# 02_CPU_SYSTEM.net
KiCad netlist of a schematic drawn in Altium Designer
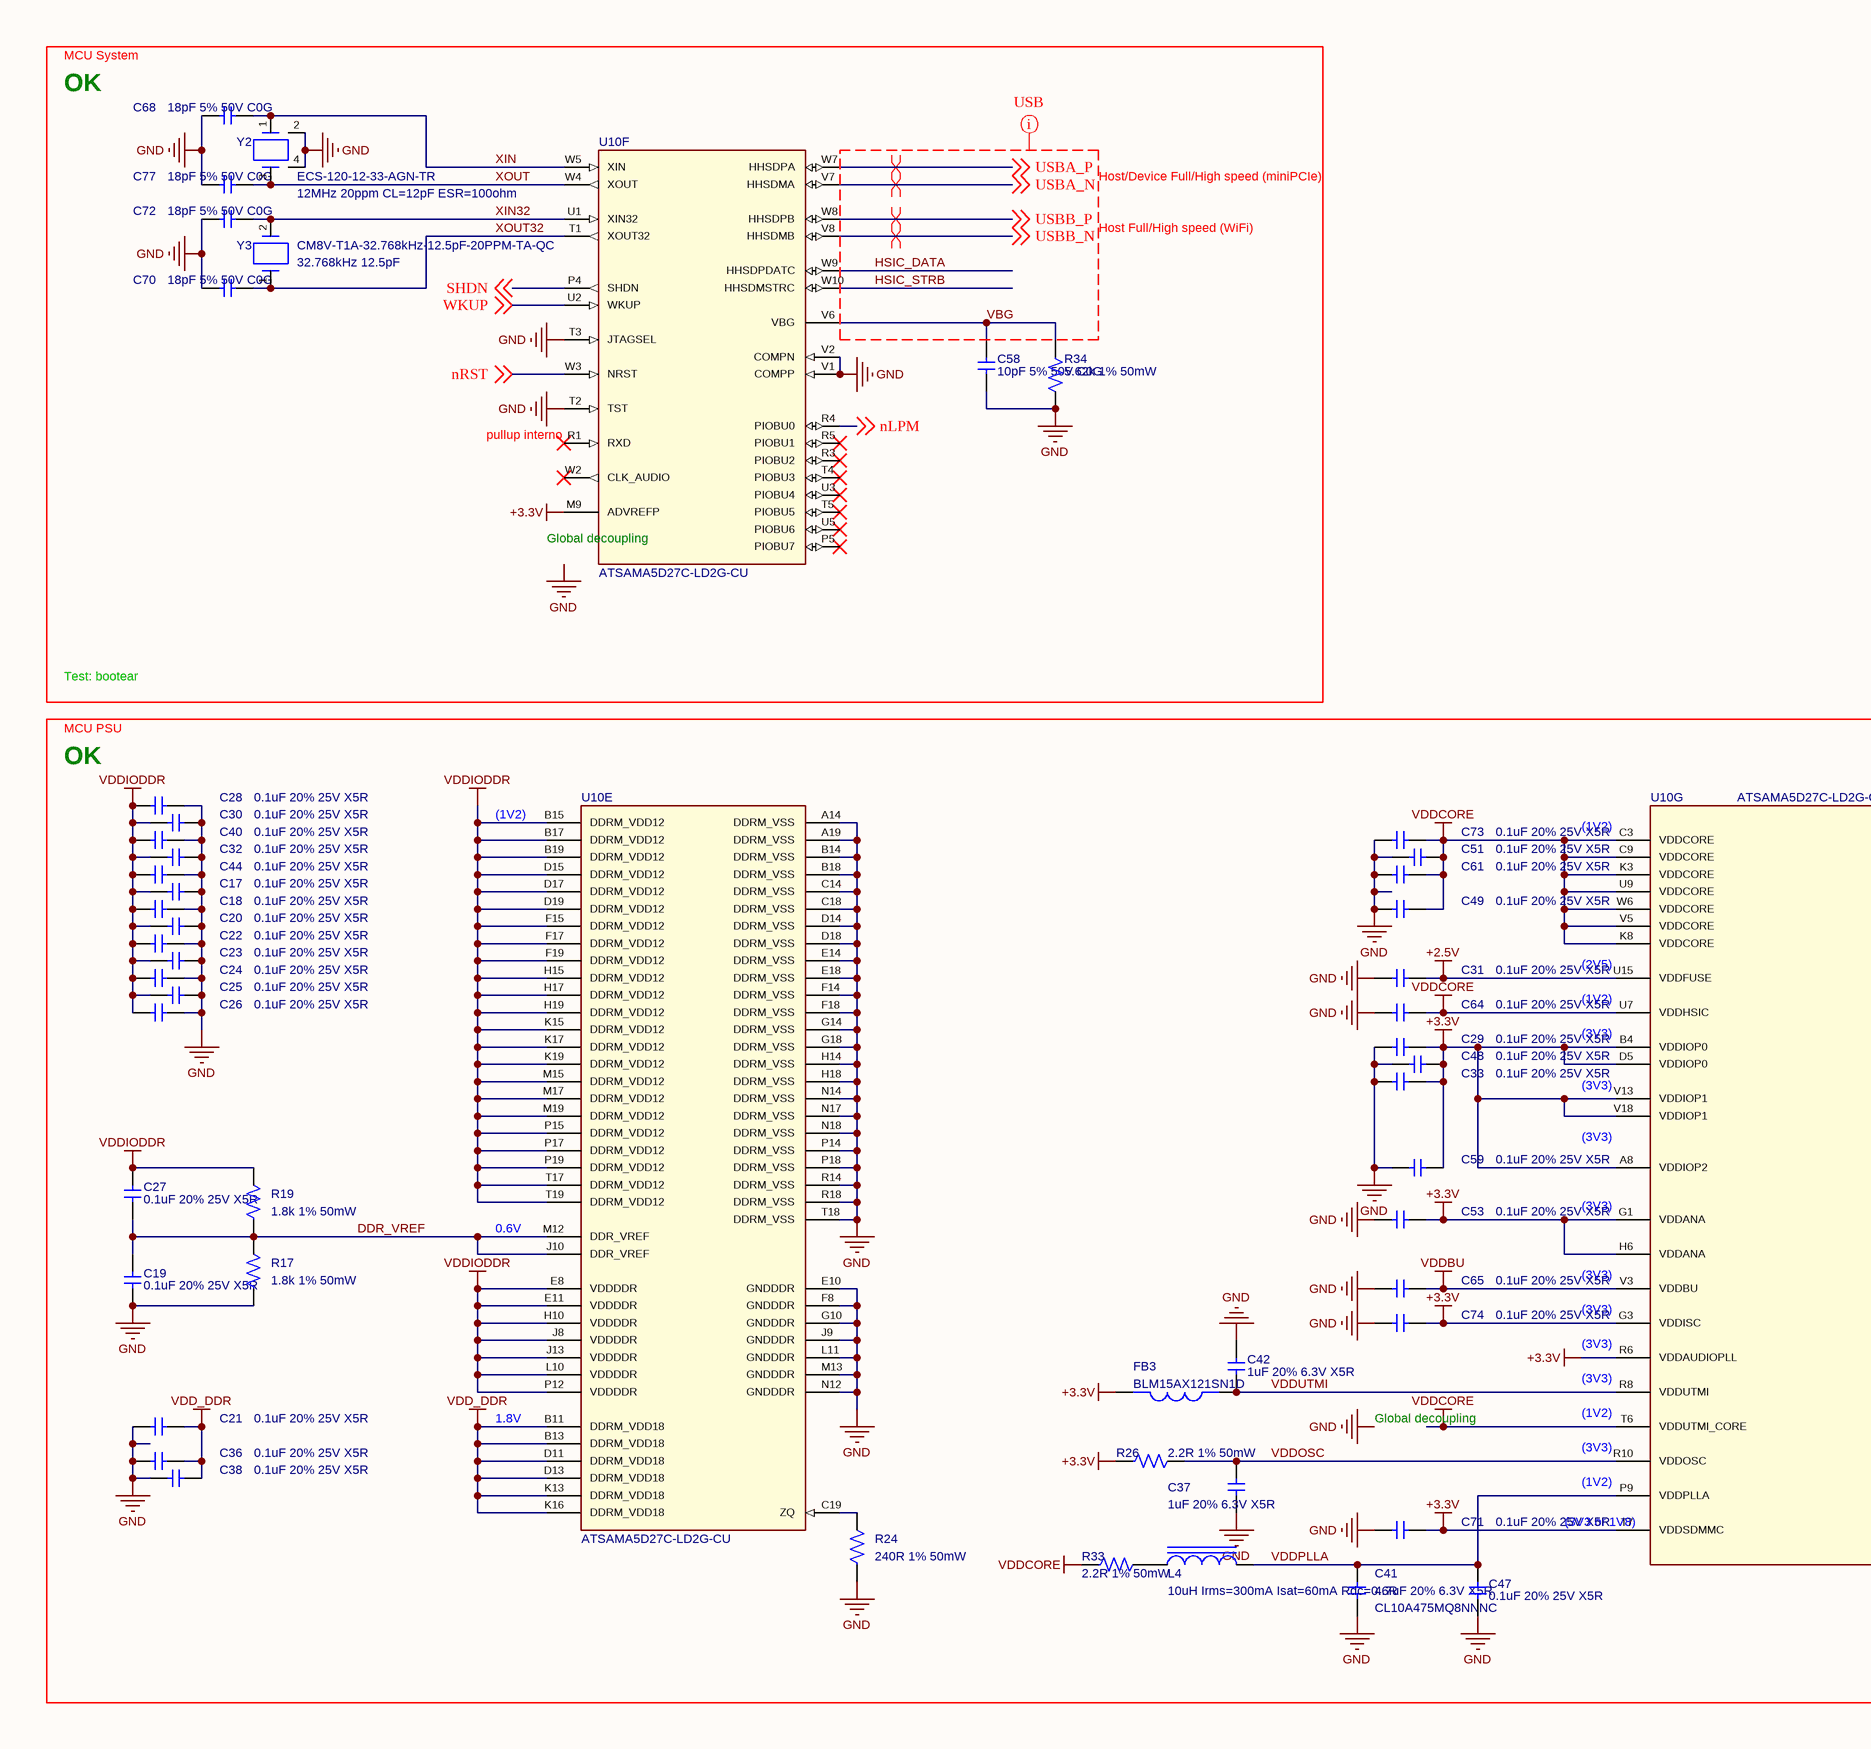
[diagram p0: 02_CPU_SYSTEM.SchDoc, left]
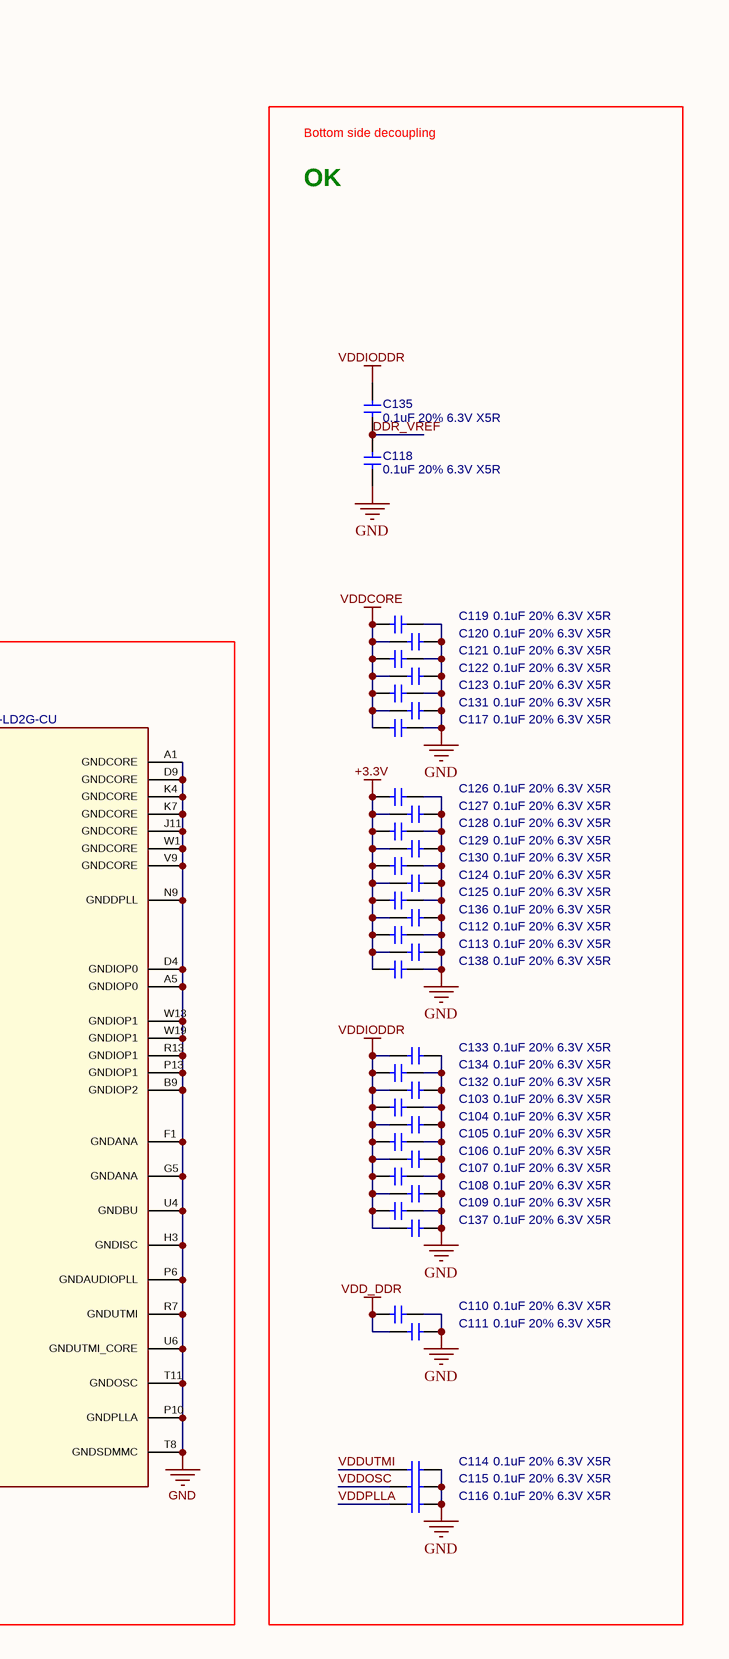
[diagram p1: 02_CPU_SYSTEM.SchDoc, right]

(export (version "E")
  (design (tool "Eeschema 10.0.6"))
  (components
    (comp (ref "C17")
      (value "0.1uF 20% 25V X5R")
      (footprint "CAPC1005N")
      (description "Capacitor, Ceramic")
      (fields (field (name "MFG") "SAMSUNG") (field (name "TOLERANCE") "20%"))
      (libsource (lib "*") (part "C_Dup1"))
    )
    (comp (ref "C18")
      (value "0.1uF 20% 25V X5R")
      (footprint "CAPC1005N")
      (description "Capacitor, Ceramic")
      (fields (field (name "MFG") "SAMSUNG") (field (name "TOLERANCE") "20%"))
      (libsource (lib "*") (part "C_Dup1"))
    )
    (comp (ref "C19")
      (value "0.1uF 20% 25V X5R")
      (footprint "CAPC1005N")
      (description "Capacitor, Ceramic")
      (fields (field (name "MFG") "SAMSUNG") (field (name "TOLERANCE") "20%"))
      (libsource (lib "*") (part "C_Dup1"))
    )
    (comp (ref "C20")
      (value "0.1uF 20% 25V X5R")
      (footprint "CAPC1005N")
      (description "Capacitor, Ceramic")
      (fields (field (name "MFG") "SAMSUNG") (field (name "TOLERANCE") "20%"))
      (libsource (lib "*") (part "C_Dup1"))
    )
    (comp (ref "C21")
      (value "0.1uF 20% 25V X5R")
      (footprint "CAPC1005N")
      (description "Capacitor, Ceramic")
      (fields (field (name "MFG") "SAMSUNG") (field (name "TOLERANCE") "20%"))
      (libsource (lib "*") (part "C_Dup1"))
    )
    (comp (ref "C22")
      (value "0.1uF 20% 25V X5R")
      (footprint "CAPC1005N")
      (description "Capacitor, Ceramic")
      (fields (field (name "MFG") "SAMSUNG") (field (name "TOLERANCE") "20%"))
      (libsource (lib "*") (part "C_Dup1"))
    )
    (comp (ref "C23")
      (value "0.1uF 20% 25V X5R")
      (footprint "CAPC1005N")
      (description "Capacitor, Ceramic")
      (fields (field (name "MFG") "SAMSUNG") (field (name "TOLERANCE") "20%"))
      (libsource (lib "*") (part "C_Dup1"))
    )
    (comp (ref "C24")
      (value "0.1uF 20% 25V X5R")
      (footprint "CAPC1005N")
      (description "Capacitor, Ceramic")
      (fields (field (name "MFG") "SAMSUNG") (field (name "TOLERANCE") "20%"))
      (libsource (lib "*") (part "C_Dup1"))
    )
    (comp (ref "C25")
      (value "0.1uF 20% 25V X5R")
      (footprint "CAPC1005N")
      (description "Capacitor, Ceramic")
      (fields (field (name "MFG") "SAMSUNG") (field (name "TOLERANCE") "20%"))
      (libsource (lib "*") (part "C_Dup1"))
    )
    (comp (ref "C26")
      (value "0.1uF 20% 25V X5R")
      (footprint "CAPC1005N")
      (description "Capacitor, Ceramic")
      (fields (field (name "MFG") "SAMSUNG") (field (name "TOLERANCE") "20%"))
      (libsource (lib "*") (part "C_Dup1"))
    )
    (comp (ref "C27")
      (value "0.1uF 20% 25V X5R")
      (footprint "CAPC1005N")
      (description "Capacitor, Ceramic")
      (fields (field (name "MFG") "SAMSUNG") (field (name "TOLERANCE") "20%"))
      (libsource (lib "*") (part "C_Dup1"))
    )
    (comp (ref "C28")
      (value "0.1uF 20% 25V X5R")
      (footprint "CAPC1005N")
      (description "Capacitor, Ceramic")
      (fields (field (name "MFG") "SAMSUNG") (field (name "TOLERANCE") "20%"))
      (libsource (lib "*") (part "C_Dup1"))
    )
    (comp (ref "C29")
      (value "0.1uF 20% 25V X5R")
      (footprint "CAPC1005N")
      (description "Capacitor, Ceramic")
      (fields (field (name "MFG") "SAMSUNG") (field (name "TOLERANCE") "20%"))
      (libsource (lib "*") (part "C_Dup1"))
    )
    (comp (ref "C30")
      (value "0.1uF 20% 25V X5R")
      (footprint "CAPC1005N")
      (description "Capacitor, Ceramic")
      (fields (field (name "MFG") "SAMSUNG") (field (name "TOLERANCE") "20%"))
      (libsource (lib "*") (part "C_Dup1"))
    )
    (comp (ref "C31")
      (value "0.1uF 20% 25V X5R")
      (footprint "CAPC1005N")
      (description "Capacitor, Ceramic")
      (fields (field (name "MFG") "SAMSUNG") (field (name "TOLERANCE") "20%"))
      (libsource (lib "*") (part "C_Dup1"))
    )
    (comp (ref "C32")
      (value "0.1uF 20% 25V X5R")
      (footprint "CAPC1005N")
      (description "Capacitor, Ceramic")
      (fields (field (name "MFG") "SAMSUNG") (field (name "TOLERANCE") "20%"))
      (libsource (lib "*") (part "C_Dup1"))
    )
    (comp (ref "C33")
      (value "0.1uF 20% 25V X5R")
      (footprint "CAPC1005N")
      (description "Capacitor, Ceramic")
      (fields (field (name "MFG") "SAMSUNG") (field (name "TOLERANCE") "20%"))
      (libsource (lib "*") (part "C_Dup1"))
    )
    (comp (ref "C36")
      (value "0.1uF 20% 25V X5R")
      (footprint "CAPC1005N")
      (description "Capacitor, Ceramic")
      (fields (field (name "MFG") "SAMSUNG") (field (name "TOLERANCE") "20%"))
      (libsource (lib "*") (part "C_Dup1"))
    )
    (comp (ref "C37")
      (value "1uF 20% 6.3V X5R")
      (footprint "CAPC1005N")
      (description "Capacitor, Ceramic")
      (fields (field (name "MFG") "SAMSUNG") (field (name "TOLERANCE") "20%"))
      (libsource (lib "*") (part "C_Dup1"))
    )
    (comp (ref "C38")
      (value "0.1uF 20% 25V X5R")
      (footprint "CAPC1005N")
      (description "Capacitor, Ceramic")
      (fields (field (name "MFG") "SAMSUNG") (field (name "TOLERANCE") "20%"))
      (libsource (lib "*") (part "C_Dup1"))
    )
    (comp (ref "C40")
      (value "0.1uF 20% 25V X5R")
      (footprint "CAPC1005N")
      (description "Capacitor, Ceramic")
      (fields (field (name "MFG") "SAMSUNG") (field (name "TOLERANCE") "20%"))
      (libsource (lib "*") (part "C_Dup1"))
    )
    (comp (ref "C41")
      (value "4.7uF 20% 6.3V X5R")
      (footprint "CAPC1608X90N")
      (description "Capacitor, Ceramic")
      (fields
        (field (name "MFG") "SAMSUNG")
        (field (name "MFG_PN") "CL10A475MQ8NNNC")
        (field (name "TOLERANCE") "20%")
      )
      (libsource (lib "*") (part "C_Dup1"))
    )
    (comp (ref "C42")
      (value "1uF 20% 6.3V X5R")
      (footprint "CAPC1005N")
      (description "Capacitor, Ceramic")
      (fields (field (name "MFG") "SAMSUNG") (field (name "TOLERANCE") "20%"))
      (libsource (lib "*") (part "C_Dup1"))
    )
    (comp (ref "C44")
      (value "0.1uF 20% 25V X5R")
      (footprint "CAPC1005N")
      (description "Capacitor, Ceramic")
      (fields (field (name "MFG") "SAMSUNG") (field (name "TOLERANCE") "20%"))
      (libsource (lib "*") (part "C_Dup1"))
    )
    (comp (ref "C47")
      (value "0.1uF 20% 25V X5R")
      (footprint "CAPC1005N")
      (description "Capacitor, Ceramic")
      (fields (field (name "MFG") "SAMSUNG") (field (name "TOLERANCE") "20%"))
      (libsource (lib "*") (part "C_Dup1"))
    )
    (comp (ref "C48")
      (value "0.1uF 20% 25V X5R")
      (footprint "CAPC1005N")
      (description "Capacitor, Ceramic")
      (fields (field (name "MFG") "SAMSUNG") (field (name "TOLERANCE") "20%"))
      (libsource (lib "*") (part "C_Dup1"))
    )
    (comp (ref "C49")
      (value "0.1uF 20% 25V X5R")
      (footprint "CAPC1005N")
      (description "Capacitor, Ceramic")
      (fields (field (name "MFG") "SAMSUNG") (field (name "TOLERANCE") "20%"))
      (libsource (lib "*") (part "C_Dup1"))
    )
    (comp (ref "C51")
      (value "0.1uF 20% 25V X5R")
      (footprint "CAPC1005N")
      (description "Capacitor, Ceramic")
      (fields (field (name "MFG") "SAMSUNG") (field (name "TOLERANCE") "20%"))
      (libsource (lib "*") (part "C_Dup1"))
    )
    (comp (ref "C53")
      (value "0.1uF 20% 25V X5R")
      (footprint "CAPC1005N")
      (description "Capacitor, Ceramic")
      (fields (field (name "MFG") "SAMSUNG") (field (name "TOLERANCE") "20%"))
      (libsource (lib "*") (part "C_Dup1"))
    )
    (comp (ref "C58")
      (value "10pF 5% 50V C0G")
      (footprint "CAPC1005N")
      (description "Capacitor, Ceramic")
      (fields (field (name "MFG") "<GENERIC>") (field (name "TOLERANCE") "5%"))
      (libsource (lib "*") (part "C_Dup1"))
    )
    (comp (ref "C59")
      (value "0.1uF 20% 25V X5R")
      (footprint "CAPC1005N")
      (description "Capacitor, Ceramic")
      (fields (field (name "MFG") "SAMSUNG") (field (name "TOLERANCE") "20%"))
      (libsource (lib "*") (part "C_Dup1"))
    )
    (comp (ref "C61")
      (value "0.1uF 20% 25V X5R")
      (footprint "CAPC1005N")
      (description "Capacitor, Ceramic")
      (fields (field (name "MFG") "SAMSUNG") (field (name "TOLERANCE") "20%"))
      (libsource (lib "*") (part "C_Dup1"))
    )
    (comp (ref "C64")
      (value "0.1uF 20% 25V X5R")
      (footprint "CAPC1005N")
      (description "Capacitor, Ceramic")
      (fields (field (name "MFG") "SAMSUNG") (field (name "TOLERANCE") "20%"))
      (libsource (lib "*") (part "C_Dup1"))
    )
    (comp (ref "C65")
      (value "0.1uF 20% 25V X5R")
      (footprint "CAPC1005N")
      (description "Capacitor, Ceramic")
      (fields (field (name "MFG") "SAMSUNG") (field (name "TOLERANCE") "20%"))
      (libsource (lib "*") (part "C_Dup1"))
    )
    (comp (ref "C68")
      (value "18pF 5% 50V C0G")
      (footprint "CAPC1005N")
      (description "Capacitor, Ceramic")
      (fields (field (name "MFG") "<GENERIC>") (field (name "TOLERANCE") "5%"))
      (libsource (lib "*") (part "C_Dup1"))
    )
    (comp (ref "C70")
      (value "18pF 5% 50V C0G")
      (footprint "CAPC1005N")
      (description "Capacitor, Ceramic")
      (fields (field (name "MFG") "<GENERIC>") (field (name "TOLERANCE") "5%"))
      (libsource (lib "*") (part "C_Dup1"))
    )
    (comp (ref "C71")
      (value "0.1uF 20% 25V X5R")
      (footprint "CAPC1005N")
      (description "Capacitor, Ceramic")
      (fields (field (name "MFG") "SAMSUNG") (field (name "TOLERANCE") "20%"))
      (libsource (lib "*") (part "C_Dup1"))
    )
    (comp (ref "C72")
      (value "18pF 5% 50V C0G")
      (footprint "CAPC1005N")
      (description "Capacitor, Ceramic")
      (fields (field (name "MFG") "<GENERIC>") (field (name "TOLERANCE") "5%"))
      (libsource (lib "*") (part "C_Dup1"))
    )
    (comp (ref "C73")
      (value "0.1uF 20% 25V X5R")
      (footprint "CAPC1005N")
      (description "Capacitor, Ceramic")
      (fields (field (name "MFG") "SAMSUNG") (field (name "TOLERANCE") "20%"))
      (libsource (lib "*") (part "C_Dup1"))
    )
    (comp (ref "C74")
      (value "0.1uF 20% 25V X5R")
      (footprint "CAPC1005N")
      (description "Capacitor, Ceramic")
      (fields (field (name "MFG") "SAMSUNG") (field (name "TOLERANCE") "20%"))
      (libsource (lib "*") (part "C_Dup1"))
    )
    (comp (ref "C77")
      (value "18pF 5% 50V C0G")
      (footprint "CAPC1005N")
      (description "Capacitor, Ceramic")
      (fields (field (name "MFG") "<GENERIC>") (field (name "TOLERANCE") "5%"))
      (libsource (lib "*") (part "C_Dup1"))
    )
    (comp (ref "C103")
      (value "0.1uF 20% 6.3V X5R")
      (footprint "CAPC0603N")
      (description "Capacitor, Ceramic")
      (fields (field (name "MFG") "SAMSUNG") (field (name "TOLERANCE") "20%"))
      (libsource (lib "*") (part "C_Dup1"))
    )
    (comp (ref "C104")
      (value "0.1uF 20% 6.3V X5R")
      (footprint "CAPC0603N")
      (description "Capacitor, Ceramic")
      (fields (field (name "MFG") "SAMSUNG") (field (name "TOLERANCE") "20%"))
      (libsource (lib "*") (part "C_Dup1"))
    )
    (comp (ref "C105")
      (value "0.1uF 20% 6.3V X5R")
      (footprint "CAPC0603N")
      (description "Capacitor, Ceramic")
      (fields (field (name "MFG") "SAMSUNG") (field (name "TOLERANCE") "20%"))
      (libsource (lib "*") (part "C_Dup1"))
    )
    (comp (ref "C106")
      (value "0.1uF 20% 6.3V X5R")
      (footprint "CAPC0603N")
      (description "Capacitor, Ceramic")
      (fields (field (name "MFG") "SAMSUNG") (field (name "TOLERANCE") "20%"))
      (libsource (lib "*") (part "C_Dup1"))
    )
    (comp (ref "C107")
      (value "0.1uF 20% 6.3V X5R")
      (footprint "CAPC0603N")
      (description "Capacitor, Ceramic")
      (fields (field (name "MFG") "SAMSUNG") (field (name "TOLERANCE") "20%"))
      (libsource (lib "*") (part "C_Dup1"))
    )
    (comp (ref "C108")
      (value "0.1uF 20% 6.3V X5R")
      (footprint "CAPC0603N")
      (description "Capacitor, Ceramic")
      (fields (field (name "MFG") "SAMSUNG") (field (name "TOLERANCE") "20%"))
      (libsource (lib "*") (part "C_Dup1"))
    )
    (comp (ref "C109")
      (value "0.1uF 20% 6.3V X5R")
      (footprint "CAPC0603N")
      (description "Capacitor, Ceramic")
      (fields (field (name "MFG") "SAMSUNG") (field (name "TOLERANCE") "20%"))
      (libsource (lib "*") (part "C_Dup1"))
    )
    (comp (ref "C110")
      (value "0.1uF 20% 6.3V X5R")
      (footprint "CAPC0603N")
      (description "Capacitor, Ceramic")
      (fields (field (name "MFG") "SAMSUNG") (field (name "TOLERANCE") "20%"))
      (libsource (lib "*") (part "C_Dup1"))
    )
    (comp (ref "C111")
      (value "0.1uF 20% 6.3V X5R")
      (footprint "CAPC0603N")
      (description "Capacitor, Ceramic")
      (fields (field (name "MFG") "SAMSUNG") (field (name "TOLERANCE") "20%"))
      (libsource (lib "*") (part "C_Dup1"))
    )
    (comp (ref "C112")
      (value "0.1uF 20% 6.3V X5R")
      (footprint "CAPC0603N")
      (description "Capacitor, Ceramic")
      (fields (field (name "MFG") "SAMSUNG") (field (name "TOLERANCE") "20%"))
      (libsource (lib "*") (part "C_Dup1"))
    )
    (comp (ref "C113")
      (value "0.1uF 20% 6.3V X5R")
      (footprint "CAPC0603N")
      (description "Capacitor, Ceramic")
      (fields (field (name "MFG") "SAMSUNG") (field (name "TOLERANCE") "20%"))
      (libsource (lib "*") (part "C_Dup1"))
    )
    (comp (ref "C114")
      (value "0.1uF 20% 6.3V X5R")
      (footprint "CAPC0603N")
      (description "Capacitor, Ceramic")
      (fields (field (name "MFG") "SAMSUNG") (field (name "TOLERANCE") "20%"))
      (libsource (lib "*") (part "C_Dup1"))
    )
    (comp (ref "C115")
      (value "0.1uF 20% 6.3V X5R")
      (footprint "CAPC0603N")
      (description "Capacitor, Ceramic")
      (fields (field (name "MFG") "SAMSUNG") (field (name "TOLERANCE") "20%"))
      (libsource (lib "*") (part "C_Dup1"))
    )
    (comp (ref "C116")
      (value "0.1uF 20% 6.3V X5R")
      (footprint "CAPC0603N")
      (description "Capacitor, Ceramic")
      (fields (field (name "MFG") "SAMSUNG") (field (name "TOLERANCE") "20%"))
      (libsource (lib "*") (part "C_Dup1"))
    )
    (comp (ref "C117")
      (value "0.1uF 20% 6.3V X5R")
      (footprint "CAPC0603N")
      (description "Capacitor, Ceramic")
      (fields (field (name "MFG") "SAMSUNG") (field (name "TOLERANCE") "20%"))
      (libsource (lib "*") (part "C_Dup1"))
    )
    (comp (ref "C118")
      (value "0.1uF 20% 6.3V X5R")
      (footprint "CAPC0603N")
      (description "Capacitor, Ceramic")
      (fields (field (name "MFG") "SAMSUNG") (field (name "TOLERANCE") "20%"))
      (libsource (lib "*") (part "C_Dup1"))
    )
    (comp (ref "C119")
      (value "0.1uF 20% 6.3V X5R")
      (footprint "CAPC0603N")
      (description "Capacitor, Ceramic")
      (fields (field (name "MFG") "SAMSUNG") (field (name "TOLERANCE") "20%"))
      (libsource (lib "*") (part "C_Dup1"))
    )
    (comp (ref "C120")
      (value "0.1uF 20% 6.3V X5R")
      (footprint "CAPC0603N")
      (description "Capacitor, Ceramic")
      (fields (field (name "MFG") "SAMSUNG") (field (name "TOLERANCE") "20%"))
      (libsource (lib "*") (part "C_Dup1"))
    )
    (comp (ref "C121")
      (value "0.1uF 20% 6.3V X5R")
      (footprint "CAPC0603N")
      (description "Capacitor, Ceramic")
      (fields (field (name "MFG") "SAMSUNG") (field (name "TOLERANCE") "20%"))
      (libsource (lib "*") (part "C_Dup1"))
    )
    (comp (ref "C122")
      (value "0.1uF 20% 6.3V X5R")
      (footprint "CAPC0603N")
      (description "Capacitor, Ceramic")
      (fields (field (name "MFG") "SAMSUNG") (field (name "TOLERANCE") "20%"))
      (libsource (lib "*") (part "C_Dup1"))
    )
    (comp (ref "C123")
      (value "0.1uF 20% 6.3V X5R")
      (footprint "CAPC0603N")
      (description "Capacitor, Ceramic")
      (fields (field (name "MFG") "SAMSUNG") (field (name "TOLERANCE") "20%"))
      (libsource (lib "*") (part "C_Dup1"))
    )
    (comp (ref "C124")
      (value "0.1uF 20% 6.3V X5R")
      (footprint "CAPC0603N")
      (description "Capacitor, Ceramic")
      (fields (field (name "MFG") "SAMSUNG") (field (name "TOLERANCE") "20%"))
      (libsource (lib "*") (part "C_Dup1"))
    )
    (comp (ref "C125")
      (value "0.1uF 20% 6.3V X5R")
      (footprint "CAPC0603N")
      (description "Capacitor, Ceramic")
      (fields (field (name "MFG") "SAMSUNG") (field (name "TOLERANCE") "20%"))
      (libsource (lib "*") (part "C_Dup1"))
    )
    (comp (ref "C126")
      (value "0.1uF 20% 6.3V X5R")
      (footprint "CAPC0603N")
      (description "Capacitor, Ceramic")
      (fields (field (name "MFG") "SAMSUNG") (field (name "TOLERANCE") "20%"))
      (libsource (lib "*") (part "C_Dup1"))
    )
    (comp (ref "C127")
      (value "0.1uF 20% 6.3V X5R")
      (footprint "CAPC0603N")
      (description "Capacitor, Ceramic")
      (fields (field (name "MFG") "SAMSUNG") (field (name "TOLERANCE") "20%"))
      (libsource (lib "*") (part "C_Dup1"))
    )
    (comp (ref "C128")
      (value "0.1uF 20% 6.3V X5R")
      (footprint "CAPC0603N")
      (description "Capacitor, Ceramic")
      (fields (field (name "MFG") "SAMSUNG") (field (name "TOLERANCE") "20%"))
      (libsource (lib "*") (part "C_Dup1"))
    )
    (comp (ref "C129")
      (value "0.1uF 20% 6.3V X5R")
      (footprint "CAPC0603N")
      (description "Capacitor, Ceramic")
      (fields (field (name "MFG") "SAMSUNG") (field (name "TOLERANCE") "20%"))
      (libsource (lib "*") (part "C_Dup1"))
    )
    (comp (ref "C130")
      (value "0.1uF 20% 6.3V X5R")
      (footprint "CAPC0603N")
      (description "Capacitor, Ceramic")
      (fields (field (name "MFG") "SAMSUNG") (field (name "TOLERANCE") "20%"))
      (libsource (lib "*") (part "C_Dup1"))
    )
    (comp (ref "C131")
      (value "0.1uF 20% 6.3V X5R")
      (footprint "CAPC0603N")
      (description "Capacitor, Ceramic")
      (fields (field (name "MFG") "SAMSUNG") (field (name "TOLERANCE") "20%"))
      (libsource (lib "*") (part "C_Dup1"))
    )
    (comp (ref "C132")
      (value "0.1uF 20% 6.3V X5R")
      (footprint "CAPC0603N")
      (description "Capacitor, Ceramic")
      (fields (field (name "MFG") "SAMSUNG") (field (name "TOLERANCE") "20%"))
      (libsource (lib "*") (part "C_Dup1"))
    )
    (comp (ref "C133")
      (value "0.1uF 20% 6.3V X5R")
      (footprint "CAPC0603N")
      (description "Capacitor, Ceramic")
      (fields (field (name "MFG") "SAMSUNG") (field (name "TOLERANCE") "20%"))
      (libsource (lib "*") (part "C_Dup1"))
    )
    (comp (ref "C134")
      (value "0.1uF 20% 6.3V X5R")
      (footprint "CAPC0603N")
      (description "Capacitor, Ceramic")
      (fields (field (name "MFG") "SAMSUNG") (field (name "TOLERANCE") "20%"))
      (libsource (lib "*") (part "C_Dup1"))
    )
    (comp (ref "C135")
      (value "0.1uF 20% 6.3V X5R")
      (footprint "CAPC0603N")
      (description "Capacitor, Ceramic")
      (fields (field (name "MFG") "SAMSUNG") (field (name "TOLERANCE") "20%"))
      (libsource (lib "*") (part "C_Dup1"))
    )
    (comp (ref "C136")
      (value "0.1uF 20% 6.3V X5R")
      (footprint "CAPC0603N")
      (description "Capacitor, Ceramic")
      (fields (field (name "MFG") "SAMSUNG") (field (name "TOLERANCE") "20%"))
      (libsource (lib "*") (part "C_Dup1"))
    )
    (comp (ref "C137")
      (value "0.1uF 20% 6.3V X5R")
      (footprint "CAPC0603N")
      (description "Capacitor, Ceramic")
      (fields (field (name "MFG") "SAMSUNG") (field (name "TOLERANCE") "20%"))
      (libsource (lib "*") (part "C_Dup1"))
    )
    (comp (ref "C138")
      (value "0.1uF 20% 6.3V X5R")
      (footprint "CAPC0603N")
      (description "Capacitor, Ceramic")
      (fields (field (name "MFG") "SAMSUNG") (field (name "TOLERANCE") "20%"))
      (libsource (lib "*") (part "C_Dup1"))
    )
    (comp (ref "FB3")
      (value "BLM15AX121SN1D")
      (footprint "INDC1005N")
      (description "Ferrite Bead")
      (fields (field (name "MFG") "MURATA"))
      (libsource (lib "*") (part "Filtre ferrites CMS-742792093"))
    )
    (comp (ref "L4")
      (value "10uH Irms=300mA Isat=60mA Rdc=0.6R")
      (footprint "INDC1608X95N")
      (description "Inductor, Ferrite core")
      (fields (field (name "MFG") "TDK"))
      (libsource (lib "components") (part "L_CORE"))
    )
    (comp (ref "R17")
      (value "1.8k 1% 50mW")
      (footprint "RESC1005X40N")
      (description "Resistor, SMD")
      (fields (field (name "MFG") "<GENERIC>") (field (name "POWER") "50mW"))
      (libsource (lib "*") (part "R"))
    )
    (comp (ref "R19")
      (value "1.8k 1% 50mW")
      (footprint "RESC1005X40N")
      (description "Resistor, SMD")
      (fields (field (name "MFG") "<GENERIC>") (field (name "POWER") "50mW"))
      (libsource (lib "*") (part "R"))
    )
    (comp (ref "R24")
      (value "240R 1% 50mW")
      (footprint "RESC1005X40N")
      (description "Resistor, SMD")
      (fields (field (name "MFG") "<GENERIC>") (field (name "POWER") "50mW"))
      (libsource (lib "*") (part "R"))
    )
    (comp (ref "R26")
      (value "2.2R 1% 50mW")
      (footprint "RESC1005X40N")
      (description "Resistor, SMD")
      (fields (field (name "MFG") "<GENERIC>") (field (name "POWER") "50mW"))
      (libsource (lib "*") (part "R"))
    )
    (comp (ref "R33")
      (value "2.2R 1% 50mW")
      (footprint "RESC1005X40N")
      (description "Resistor, SMD")
      (fields (field (name "MFG") "<GENERIC>") (field (name "POWER") "50mW"))
      (libsource (lib "*") (part "R"))
    )
    (comp (ref "R34")
      (value "5.62k 1% 50mW")
      (footprint "RESC1005X40N")
      (description "Resistor, SMD")
      (fields (field (name "MFG") "<GENERIC>") (field (name "POWER") "50mW"))
      (libsource (lib "*") (part "R"))
    )
    (comp (ref "U10")
      (value "ATSAMA5D27C-LD2G-CU")
      (footprint "TFBGA-361-16X16")
      (description "SAMA5D2 MPU with 2Gb LPDDR2 x32 TFBGA-361")
      (fields (field (name "MFG") "MICROCHIP"))
      (libsource (lib "") (part "SAMA5D2-LPDDR2-SIP-BGA-361_1"))
    )
    (comp (ref "Y2")
      (value "ECS-120-12-33-AGN-TR")
      (footprint "SensorWireless:XTAL3.2x2.5")
      (description "Crystal")
      (fields (field (name "MFG") "ECS") (field (name "ALTIUM_VALUE") "12MHz 20ppm CL=12pF ESR=100ohm"))
      (libsource (lib "sch") (part "CS10-12MHz"))
    )
    (comp (ref "Y3")
      (value "CM8V-T1A-32.768kHz-12.5pF-20PPM-TA-QC")
      (footprint "SensorWireless:XTAL2.0x1.2")
      (description "Crystal")
      (fields (field (name "MFG") "TXC") (field (name "ALTIUM_VALUE") "32.768kHz 12.5pF"))
      (libsource (lib "*") (part "CS10-12MHz"))
    )
  )
  (nets
    (net (code "1") (name "+2.5V") (class "Default")
      (node (ref "C31") (pin "1") (pinfunction "1_1") (pintype "passive"))
      (node (ref "U10") (pin "U15") (pinfunction "VDDFUSE_U15") (pintype "power_in"))
    )
    (net (code "2") (name "+3.3V") (class "Default")
      (node (ref "C112") (pin "1") (pinfunction "1_1") (pintype "passive"))
      (node (ref "C113") (pin "1") (pinfunction "1_1") (pintype "passive"))
      (node (ref "C124") (pin "1") (pinfunction "1_1") (pintype "passive"))
      (node (ref "C125") (pin "1") (pinfunction "1_1") (pintype "passive"))
      (node (ref "C126") (pin "1") (pinfunction "1_1") (pintype "passive"))
      (node (ref "C127") (pin "1") (pinfunction "1_1") (pintype "passive"))
      (node (ref "C128") (pin "1") (pinfunction "1_1") (pintype "passive"))
      (node (ref "C129") (pin "1") (pinfunction "1_1") (pintype "passive"))
      (node (ref "C130") (pin "1") (pinfunction "1_1") (pintype "passive"))
      (node (ref "C136") (pin "1") (pinfunction "1_1") (pintype "passive"))
      (node (ref "C138") (pin "1") (pinfunction "1_1") (pintype "passive"))
      (node (ref "C29") (pin "2") (pinfunction "2_2") (pintype "passive"))
      (node (ref "C33") (pin "2") (pinfunction "2_2") (pintype "passive"))
      (node (ref "C48") (pin "2") (pinfunction "2_2") (pintype "passive"))
      (node (ref "C53") (pin "1") (pinfunction "1_1") (pintype "passive"))
      (node (ref "C59") (pin "2") (pinfunction "2_2") (pintype "passive"))
      (node (ref "C71") (pin "2") (pinfunction "2_2") (pintype "passive"))
      (node (ref "C74") (pin "2") (pinfunction "2_2") (pintype "passive"))
      (node (ref "FB3") (pin "1") (pinfunction "1_1") (pintype "passive"))
      (node (ref "R26") (pin "1") (pinfunction "1_1") (pintype "passive"))
      (node (ref "U10") (pin "A8") (pinfunction "VDDIOP2_A8") (pintype "power_in"))
      (node (ref "U10") (pin "B4") (pinfunction "VDDIOP0_B4") (pintype "power_in"))
      (node (ref "U10") (pin "D5") (pinfunction "VDDIOP0_D5") (pintype "power_in"))
      (node (ref "U10") (pin "G1") (pinfunction "VDDANA_G1") (pintype "power_in"))
      (node (ref "U10") (pin "G3") (pinfunction "VDDISC_G3") (pintype "power_in"))
      (node (ref "U10") (pin "H6") (pinfunction "VDDANA_H6") (pintype "power_in"))
      (node (ref "U10") (pin "M9") (pinfunction "ADVREFP_M9") (pintype "power_in"))
      (node (ref "U10") (pin "R6") (pinfunction "VDDAUDIOPLL_R6") (pintype "power_in"))
      (node (ref "U10") (pin "T7") (pinfunction "VDDSDMMC_T7") (pintype "power_in"))
      (node (ref "U10") (pin "V13") (pinfunction "VDDIOP1_V13") (pintype "power_in"))
      (node (ref "U10") (pin "V18") (pinfunction "VDDIOP1_V18") (pintype "power_in"))
    )
    (net (code "3") (name "/DDR_VREF") (class "Default")
      (node (ref "C118") (pin "1") (pinfunction "1_1") (pintype "passive"))
      (node (ref "C135") (pin "1") (pinfunction "1_1") (pintype "passive"))
      (node (ref "C19") (pin "2") (pinfunction "2_2") (pintype "passive"))
      (node (ref "C27") (pin "1") (pinfunction "1_1") (pintype "passive"))
      (node (ref "R17") (pin "2") (pinfunction "2_2") (pintype "passive"))
      (node (ref "R19") (pin "1") (pinfunction "1_1") (pintype "passive"))
      (node (ref "U10") (pin "J10") (pinfunction "DDR_VREF-02_J10") (pintype "power_in"))
      (node (ref "U10") (pin "M12") (pinfunction "DDR_VREF-01_M12") (pintype "power_in"))
    )
    (net (code "4") (name "/HSIC_DATA") (class "Default")
      (node (ref "U10") (pin "W9") (pinfunction "HHSDPDATC_W9") (pintype "bidirectional"))
    )
    (net (code "5") (name "/HSIC_STRB") (class "Default")
      (node (ref "U10") (pin "W10") (pinfunction "HHSDMSTRC_W10") (pintype "bidirectional"))
    )
    (net (code "6") (name "/VBG") (class "Default")
      (node (ref "C58") (pin "2") (pinfunction "2_2") (pintype "passive"))
      (node (ref "R34") (pin "1") (pinfunction "1_1") (pintype "passive"))
      (node (ref "U10") (pin "V6") (pinfunction "VBG_V6") (pintype "power_in"))
    )
    (net (code "7") (name "/VDDOSC") (class "Default")
      (node (ref "C115") (pin "1") (pinfunction "1_1") (pintype "passive"))
      (node (ref "C37") (pin "1") (pinfunction "1_1") (pintype "passive"))
      (node (ref "R26") (pin "2") (pinfunction "2_2") (pintype "passive"))
      (node (ref "U10") (pin "R10") (pinfunction "VDDOSC_R10") (pintype "power_in"))
    )
    (net (code "8") (name "/VDDPLLA") (class "Default")
      (node (ref "C116") (pin "1") (pinfunction "1_1") (pintype "passive"))
      (node (ref "C41") (pin "1") (pinfunction "1_1") (pintype "passive"))
      (node (ref "C47") (pin "2") (pinfunction "2_2") (pintype "passive"))
      (node (ref "L4") (pin "2") (pinfunction "2_2") (pintype "passive"))
      (node (ref "U10") (pin "P9") (pinfunction "VDDPLLA_P9") (pintype "power_in"))
    )
    (net (code "9") (name "/VDDUTMI") (class "Default")
      (node (ref "C114") (pin "1") (pinfunction "1_1") (pintype "passive"))
      (node (ref "C42") (pin "1") (pinfunction "1_1") (pintype "passive"))
      (node (ref "FB3") (pin "2") (pinfunction "2_2") (pintype "passive"))
      (node (ref "U10") (pin "R8") (pinfunction "VDDUTMI_R8") (pintype "power_in"))
    )
    (net (code "10") (name "/XIN") (class "Default")
      (node (ref "C68") (pin "2") (pinfunction "2_2") (pintype "passive"))
      (node (ref "U10") (pin "W5") (pinfunction "XIN_W5") (pintype "input"))
      (node (ref "Y2") (pin "1") (pinfunction "S1_1") (pintype "passive"))
    )
    (net (code "11") (name "/XIN32") (class "Default")
      (node (ref "C72") (pin "2") (pinfunction "2_2") (pintype "passive"))
      (node (ref "U10") (pin "U1") (pinfunction "XIN32_U1") (pintype "input"))
      (node (ref "Y3") (pin "2") (pinfunction "S2_2") (pintype "passive"))
    )
    (net (code "12") (name "/XOUT") (class "Default")
      (node (ref "C77") (pin "2") (pinfunction "2_2") (pintype "passive"))
      (node (ref "U10") (pin "W4") (pinfunction "XOUT_W4") (pintype "output"))
      (node (ref "Y2") (pin "3") (pinfunction "S2_3") (pintype "passive"))
    )
    (net (code "13") (name "/XOUT32") (class "Default")
      (node (ref "C70") (pin "2") (pinfunction "2_2") (pintype "passive"))
      (node (ref "U10") (pin "T1") (pinfunction "XOUT32_T1") (pintype "output"))
      (node (ref "Y3") (pin "1") (pinfunction "S1_1") (pintype "passive"))
    )
    (net (code "14") (name "GND") (class "Default")
      (node (ref "C103") (pin "2") (pinfunction "2_2") (pintype "passive"))
      (node (ref "C104") (pin "2") (pinfunction "2_2") (pintype "passive"))
      (node (ref "C105") (pin "2") (pinfunction "2_2") (pintype "passive"))
      (node (ref "C106") (pin "2") (pinfunction "2_2") (pintype "passive"))
      (node (ref "C107") (pin "2") (pinfunction "2_2") (pintype "passive"))
      (node (ref "C108") (pin "2") (pinfunction "2_2") (pintype "passive"))
      (node (ref "C109") (pin "2") (pinfunction "2_2") (pintype "passive"))
      (node (ref "C110") (pin "2") (pinfunction "2_2") (pintype "passive"))
      (node (ref "C111") (pin "2") (pinfunction "2_2") (pintype "passive"))
      (node (ref "C112") (pin "2") (pinfunction "2_2") (pintype "passive"))
      (node (ref "C113") (pin "2") (pinfunction "2_2") (pintype "passive"))
      (node (ref "C114") (pin "2") (pinfunction "2_2") (pintype "passive"))
      (node (ref "C115") (pin "2") (pinfunction "2_2") (pintype "passive"))
      (node (ref "C116") (pin "2") (pinfunction "2_2") (pintype "passive"))
      (node (ref "C117") (pin "2") (pinfunction "2_2") (pintype "passive"))
      (node (ref "C118") (pin "2") (pinfunction "2_2") (pintype "passive"))
      (node (ref "C119") (pin "2") (pinfunction "2_2") (pintype "passive"))
      (node (ref "C120") (pin "2") (pinfunction "2_2") (pintype "passive"))
      (node (ref "C121") (pin "2") (pinfunction "2_2") (pintype "passive"))
      (node (ref "C122") (pin "2") (pinfunction "2_2") (pintype "passive"))
      (node (ref "C123") (pin "2") (pinfunction "2_2") (pintype "passive"))
      (node (ref "C124") (pin "2") (pinfunction "2_2") (pintype "passive"))
      (node (ref "C125") (pin "2") (pinfunction "2_2") (pintype "passive"))
      (node (ref "C126") (pin "2") (pinfunction "2_2") (pintype "passive"))
      (node (ref "C127") (pin "2") (pinfunction "2_2") (pintype "passive"))
      (node (ref "C128") (pin "2") (pinfunction "2_2") (pintype "passive"))
      (node (ref "C129") (pin "2") (pinfunction "2_2") (pintype "passive"))
      (node (ref "C130") (pin "2") (pinfunction "2_2") (pintype "passive"))
      (node (ref "C131") (pin "2") (pinfunction "2_2") (pintype "passive"))
      (node (ref "C132") (pin "2") (pinfunction "2_2") (pintype "passive"))
      (node (ref "C133") (pin "2") (pinfunction "2_2") (pintype "passive"))
      (node (ref "C134") (pin "2") (pinfunction "2_2") (pintype "passive"))
      (node (ref "C136") (pin "2") (pinfunction "2_2") (pintype "passive"))
      (node (ref "C137") (pin "2") (pinfunction "2_2") (pintype "passive"))
      (node (ref "C138") (pin "2") (pinfunction "2_2") (pintype "passive"))
      (node (ref "C17") (pin "2") (pinfunction "2_2") (pintype "passive"))
      (node (ref "C18") (pin "2") (pinfunction "2_2") (pintype "passive"))
      (node (ref "C19") (pin "1") (pinfunction "1_1") (pintype "passive"))
      (node (ref "C20") (pin "2") (pinfunction "2_2") (pintype "passive"))
      (node (ref "C21") (pin "1") (pinfunction "1_1") (pintype "passive"))
      (node (ref "C22") (pin "2") (pinfunction "2_2") (pintype "passive"))
      (node (ref "C23") (pin "2") (pinfunction "2_2") (pintype "passive"))
      (node (ref "C24") (pin "2") (pinfunction "2_2") (pintype "passive"))
      (node (ref "C25") (pin "2") (pinfunction "2_2") (pintype "passive"))
      (node (ref "C26") (pin "2") (pinfunction "2_2") (pintype "passive"))
      (node (ref "C28") (pin "2") (pinfunction "2_2") (pintype "passive"))
      (node (ref "C29") (pin "1") (pinfunction "1_1") (pintype "passive"))
      (node (ref "C30") (pin "2") (pinfunction "2_2") (pintype "passive"))
      (node (ref "C31") (pin "2") (pinfunction "2_2") (pintype "passive"))
      (node (ref "C32") (pin "2") (pinfunction "2_2") (pintype "passive"))
      (node (ref "C33") (pin "1") (pinfunction "1_1") (pintype "passive"))
      (node (ref "C36") (pin "1") (pinfunction "1_1") (pintype "passive"))
      (node (ref "C37") (pin "2") (pinfunction "2_2") (pintype "passive"))
      (node (ref "C38") (pin "1") (pinfunction "1_1") (pintype "passive"))
      (node (ref "C40") (pin "2") (pinfunction "2_2") (pintype "passive"))
      (node (ref "C41") (pin "2") (pinfunction "2_2") (pintype "passive"))
      (node (ref "C42") (pin "2") (pinfunction "2_2") (pintype "passive"))
      (node (ref "C44") (pin "2") (pinfunction "2_2") (pintype "passive"))
      (node (ref "C47") (pin "1") (pinfunction "1_1") (pintype "passive"))
      (node (ref "C48") (pin "1") (pinfunction "1_1") (pintype "passive"))
      (node (ref "C49") (pin "1") (pinfunction "1_1") (pintype "passive"))
      (node (ref "C51") (pin "1") (pinfunction "1_1") (pintype "passive"))
      (node (ref "C53") (pin "2") (pinfunction "2_2") (pintype "passive"))
      (node (ref "C58") (pin "1") (pinfunction "1_1") (pintype "passive"))
      (node (ref "C59") (pin "1") (pinfunction "1_1") (pintype "passive"))
      (node (ref "C61") (pin "1") (pinfunction "1_1") (pintype "passive"))
      (node (ref "C64") (pin "1") (pinfunction "1_1") (pintype "passive"))
      (node (ref "C65") (pin "2") (pinfunction "2_2") (pintype "passive"))
      (node (ref "C68") (pin "1") (pinfunction "1_1") (pintype "passive"))
      (node (ref "C70") (pin "1") (pinfunction "1_1") (pintype "passive"))
      (node (ref "C71") (pin "1") (pinfunction "1_1") (pintype "passive"))
      (node (ref "C72") (pin "1") (pinfunction "1_1") (pintype "passive"))
      (node (ref "C73") (pin "1") (pinfunction "1_1") (pintype "passive"))
      (node (ref "C74") (pin "1") (pinfunction "1_1") (pintype "passive"))
      (node (ref "C77") (pin "1") (pinfunction "1_1") (pintype "passive"))
      (node (ref "R17") (pin "1") (pinfunction "1_1") (pintype "passive"))
      (node (ref "R24") (pin "1") (pinfunction "1_1") (pintype "passive"))
      (node (ref "R34") (pin "2") (pinfunction "2_2") (pintype "passive"))
      (node (ref "U10") (pin "A1") (pinfunction "GNDCORE_A1") (pintype "power_in"))
      (node (ref "U10") (pin "A14") (pinfunction "DDRM_VSS_A14") (pintype "power_in"))
      (node (ref "U10") (pin "A19") (pinfunction "DDRM_VSS_A19") (pintype "power_in"))
      (node (ref "U10") (pin "A5") (pinfunction "GNDIOP0_A5") (pintype "power_in"))
      (node (ref "U10") (pin "B14") (pinfunction "DDRM_VSS_B14") (pintype "power_in"))
      (node (ref "U10") (pin "B18") (pinfunction "DDRM_VSS_B18") (pintype "power_in"))
      (node (ref "U10") (pin "B9") (pinfunction "GNDIOP2_B9") (pintype "power_in"))
      (node (ref "U10") (pin "C14") (pinfunction "DDRM_VSS_C14") (pintype "power_in"))
      (node (ref "U10") (pin "C18") (pinfunction "DDRM_VSS_C18") (pintype "power_in"))
      (node (ref "U10") (pin "D14") (pinfunction "DDRM_VSS_D14") (pintype "power_in"))
      (node (ref "U10") (pin "D18") (pinfunction "DDRM_VSS_D18") (pintype "power_in"))
      (node (ref "U10") (pin "D4") (pinfunction "GNDIOP0_D4") (pintype "power_in"))
      (node (ref "U10") (pin "D9") (pinfunction "GNDCORE_D9") (pintype "power_in"))
      (node (ref "U10") (pin "E10") (pinfunction "GNDDDR_E10") (pintype "power_in"))
      (node (ref "U10") (pin "E14") (pinfunction "DDRM_VSS_E14") (pintype "power_in"))
      (node (ref "U10") (pin "E18") (pinfunction "DDRM_VSS_E18") (pintype "power_in"))
      (node (ref "U10") (pin "F1") (pinfunction "GNDANA_F1") (pintype "power_in"))
      (node (ref "U10") (pin "F14") (pinfunction "DDRM_VSS_F14") (pintype "power_in"))
      (node (ref "U10") (pin "F18") (pinfunction "DDRM_VSS_F18") (pintype "power_in"))
      (node (ref "U10") (pin "F8") (pinfunction "GNDDDR_F8") (pintype "power_in"))
      (node (ref "U10") (pin "G10") (pinfunction "GNDDDR_G10") (pintype "power_in"))
      (node (ref "U10") (pin "G14") (pinfunction "DDRM_VSS_G14") (pintype "power_in"))
      (node (ref "U10") (pin "G18") (pinfunction "DDRM_VSS_G18") (pintype "power_in"))
      (node (ref "U10") (pin "G5") (pinfunction "GNDANA_G5") (pintype "power_in"))
      (node (ref "U10") (pin "H14") (pinfunction "DDRM_VSS_H14") (pintype "power_in"))
      (node (ref "U10") (pin "H18") (pinfunction "DDRM_VSS_H18") (pintype "power_in"))
      (node (ref "U10") (pin "H3") (pinfunction "GNDISC_H3") (pintype "power_in"))
      (node (ref "U10") (pin "J11") (pinfunction "GNDCORE_J11") (pintype "power_in"))
      (node (ref "U10") (pin "J9") (pinfunction "GNDDDR_J9") (pintype "power_in"))
      (node (ref "U10") (pin "K4") (pinfunction "GNDCORE_K4") (pintype "power_in"))
      (node (ref "U10") (pin "K7") (pinfunction "GNDCORE_K7") (pintype "power_in"))
      (node (ref "U10") (pin "L11") (pinfunction "GNDDDR_L11") (pintype "power_in"))
      (node (ref "U10") (pin "M13") (pinfunction "GNDDDR_M13") (pintype "power_in"))
      (node (ref "U10") (pin "N12") (pinfunction "GNDDDR_N12") (pintype "power_in"))
      (node (ref "U10") (pin "N14") (pinfunction "DDRM_VSS_N14") (pintype "power_in"))
      (node (ref "U10") (pin "N17") (pinfunction "DDRM_VSS_N17") (pintype "power_in"))
      (node (ref "U10") (pin "N18") (pinfunction "DDRM_VSS_N18") (pintype "power_in"))
      (node (ref "U10") (pin "N9") (pinfunction "GNDDPLL_N9") (pintype "power_in"))
      (node (ref "U10") (pin "P10") (pinfunction "GNDPLLA_P10") (pintype "power_in"))
      (node (ref "U10") (pin "P13") (pinfunction "GNDIOP1_P13") (pintype "power_in"))
      (node (ref "U10") (pin "P14") (pinfunction "DDRM_VSS_P14") (pintype "power_in"))
      (node (ref "U10") (pin "P18") (pinfunction "DDRM_VSS_P18") (pintype "power_in"))
      (node (ref "U10") (pin "P6") (pinfunction "GNDAUDIOPLL_P6") (pintype "power_in"))
      (node (ref "U10") (pin "R13") (pinfunction "GNDIOP1_R13") (pintype "power_in"))
      (node (ref "U10") (pin "R14") (pinfunction "DDRM_VSS_R14") (pintype "power_in"))
      (node (ref "U10") (pin "R18") (pinfunction "DDRM_VSS_R18") (pintype "power_in"))
      (node (ref "U10") (pin "R7") (pinfunction "GNDUTMI_R7") (pintype "power_in"))
      (node (ref "U10") (pin "T11") (pinfunction "GNDOSC_T11") (pintype "power_in"))
      (node (ref "U10") (pin "T18") (pinfunction "DDRM_VSS_T18") (pintype "power_in"))
      (node (ref "U10") (pin "T2") (pinfunction "TST_T2") (pintype "input"))
      (node (ref "U10") (pin "T3") (pinfunction "JTAGSEL_T3") (pintype "input"))
      (node (ref "U10") (pin "T8") (pinfunction "GNDSDMMC_T8") (pintype "power_in"))
      (node (ref "U10") (pin "U4") (pinfunction "GNDBU_U4") (pintype "power_in"))
      (node (ref "U10") (pin "U6") (pinfunction "GNDUTMI_CORE_U6") (pintype "power_in"))
      (node (ref "U10") (pin "V1") (pinfunction "COMPP_V1") (pintype "input"))
      (node (ref "U10") (pin "V2") (pinfunction "COMPN_V2") (pintype "input"))
      (node (ref "U10") (pin "V9") (pinfunction "GNDCORE_V9") (pintype "power_in"))
      (node (ref "U10") (pin "W1") (pinfunction "GNDCORE_W1") (pintype "power_in"))
      (node (ref "U10") (pin "W13") (pinfunction "GNDIOP1_W13") (pintype "power_in"))
      (node (ref "U10") (pin "W19") (pinfunction "GNDIOP1_W19") (pintype "power_in"))
      (node (ref "Y2") (pin "2") (pinfunction "GND_2") (pintype "passive"))
      (node (ref "Y2") (pin "4") (pinfunction "GND_4") (pintype "passive"))
    )
    (net (code "15") (name "Net-(L4-Pad1)") (class "Default")
      (node (ref "L4") (pin "1") (pinfunction "1_1") (pintype "passive"))
      (node (ref "R33") (pin "2") (pinfunction "2_2") (pintype "passive"))
    )
    (net (code "16") (name "Net-(U10E-ZQ)") (class "Default")
      (node (ref "R24") (pin "2") (pinfunction "2_2") (pintype "passive"))
      (node (ref "U10") (pin "C19") (pinfunction "ZQ_C19") (pintype "input"))
    )
    (net (code "17") (name "SHDN") (class "Default")
      (node (ref "U10") (pin "P4") (pinfunction "SHDN_P4") (pintype "output"))
    )
    (net (code "18") (name "USBA_N") (class "Default")
      (node (ref "U10") (pin "V7") (pinfunction "HHSDMA_V7") (pintype "bidirectional"))
    )
    (net (code "19") (name "USBA_P") (class "Default")
      (node (ref "U10") (pin "W7") (pinfunction "HHSDPA_W7") (pintype "bidirectional"))
    )
    (net (code "20") (name "USBB_N") (class "Default")
      (node (ref "U10") (pin "V8") (pinfunction "HHSDMB_V8") (pintype "bidirectional"))
    )
    (net (code "21") (name "USBB_P") (class "Default")
      (node (ref "U10") (pin "W8") (pinfunction "HHSDPB_W8") (pintype "bidirectional"))
    )
    (net (code "22") (name "VDDBU") (class "Default")
      (node (ref "C65") (pin "1") (pinfunction "1_1") (pintype "passive"))
      (node (ref "U10") (pin "V3") (pinfunction "VDDBU_V3") (pintype "power_in"))
    )
    (net (code "23") (name "VDDCORE") (class "Default")
      (node (ref "C117") (pin "1") (pinfunction "1_1") (pintype "passive"))
      (node (ref "C119") (pin "1") (pinfunction "1_1") (pintype "passive"))
      (node (ref "C120") (pin "1") (pinfunction "1_1") (pintype "passive"))
      (node (ref "C121") (pin "1") (pinfunction "1_1") (pintype "passive"))
      (node (ref "C122") (pin "1") (pinfunction "1_1") (pintype "passive"))
      (node (ref "C123") (pin "1") (pinfunction "1_1") (pintype "passive"))
      (node (ref "C131") (pin "1") (pinfunction "1_1") (pintype "passive"))
      (node (ref "C49") (pin "2") (pinfunction "2_2") (pintype "passive"))
      (node (ref "C51") (pin "2") (pinfunction "2_2") (pintype "passive"))
      (node (ref "C61") (pin "2") (pinfunction "2_2") (pintype "passive"))
      (node (ref "C64") (pin "2") (pinfunction "2_2") (pintype "passive"))
      (node (ref "C73") (pin "2") (pinfunction "2_2") (pintype "passive"))
      (node (ref "R33") (pin "1") (pinfunction "1_1") (pintype "passive"))
      (node (ref "U10") (pin "C3") (pinfunction "VDDCORE_C3") (pintype "power_in"))
      (node (ref "U10") (pin "C9") (pinfunction "VDDCORE_C9") (pintype "power_in"))
      (node (ref "U10") (pin "K3") (pinfunction "VDDCORE_K3") (pintype "power_in"))
      (node (ref "U10") (pin "K8") (pinfunction "VDDCORE_K8") (pintype "power_in"))
      (node (ref "U10") (pin "T6") (pinfunction "VDDUTMI_CORE_T6") (pintype "power_in"))
      (node (ref "U10") (pin "U7") (pinfunction "VDDHSIC_U7") (pintype "power_in"))
      (node (ref "U10") (pin "U9") (pinfunction "VDDCORE_U9") (pintype "power_in"))
      (node (ref "U10") (pin "V5") (pinfunction "VDDCORE_V5") (pintype "power_in"))
      (node (ref "U10") (pin "W6") (pinfunction "VDDCORE_W6") (pintype "power_in"))
    )
    (net (code "24") (name "VDDIODDR") (class "Default")
      (node (ref "C103") (pin "1") (pinfunction "1_1") (pintype "passive"))
      (node (ref "C104") (pin "1") (pinfunction "1_1") (pintype "passive"))
      (node (ref "C105") (pin "1") (pinfunction "1_1") (pintype "passive"))
      (node (ref "C106") (pin "1") (pinfunction "1_1") (pintype "passive"))
      (node (ref "C107") (pin "1") (pinfunction "1_1") (pintype "passive"))
      (node (ref "C108") (pin "1") (pinfunction "1_1") (pintype "passive"))
      (node (ref "C109") (pin "1") (pinfunction "1_1") (pintype "passive"))
      (node (ref "C132") (pin "1") (pinfunction "1_1") (pintype "passive"))
      (node (ref "C133") (pin "1") (pinfunction "1_1") (pintype "passive"))
      (node (ref "C134") (pin "1") (pinfunction "1_1") (pintype "passive"))
      (node (ref "C135") (pin "2") (pinfunction "2_2") (pintype "passive"))
      (node (ref "C137") (pin "1") (pinfunction "1_1") (pintype "passive"))
      (node (ref "C17") (pin "1") (pinfunction "1_1") (pintype "passive"))
      (node (ref "C18") (pin "1") (pinfunction "1_1") (pintype "passive"))
      (node (ref "C20") (pin "1") (pinfunction "1_1") (pintype "passive"))
      (node (ref "C22") (pin "1") (pinfunction "1_1") (pintype "passive"))
      (node (ref "C23") (pin "1") (pinfunction "1_1") (pintype "passive"))
      (node (ref "C24") (pin "1") (pinfunction "1_1") (pintype "passive"))
      (node (ref "C25") (pin "1") (pinfunction "1_1") (pintype "passive"))
      (node (ref "C26") (pin "1") (pinfunction "1_1") (pintype "passive"))
      (node (ref "C27") (pin "2") (pinfunction "2_2") (pintype "passive"))
      (node (ref "C28") (pin "1") (pinfunction "1_1") (pintype "passive"))
      (node (ref "C30") (pin "1") (pinfunction "1_1") (pintype "passive"))
      (node (ref "C32") (pin "1") (pinfunction "1_1") (pintype "passive"))
      (node (ref "C40") (pin "1") (pinfunction "1_1") (pintype "passive"))
      (node (ref "C44") (pin "1") (pinfunction "1_1") (pintype "passive"))
      (node (ref "R19") (pin "2") (pinfunction "2_2") (pintype "passive"))
      (node (ref "U10") (pin "B15") (pinfunction "DDRM_VDD12_B15") (pintype "power_in"))
      (node (ref "U10") (pin "B17") (pinfunction "DDRM_VDD12_B17") (pintype "power_in"))
      (node (ref "U10") (pin "B19") (pinfunction "DDRM_VDD12_B19") (pintype "power_in"))
      (node (ref "U10") (pin "D15") (pinfunction "DDRM_VDD12_D15") (pintype "power_in"))
      (node (ref "U10") (pin "D17") (pinfunction "DDRM_VDD12_D17") (pintype "power_in"))
      (node (ref "U10") (pin "D19") (pinfunction "DDRM_VDD12_D19") (pintype "power_in"))
      (node (ref "U10") (pin "E11") (pinfunction "VDDDDR_E11") (pintype "power_in"))
      (node (ref "U10") (pin "E8") (pinfunction "VDDDDR_E8") (pintype "power_in"))
      (node (ref "U10") (pin "F15") (pinfunction "DDRM_VDD12_F15") (pintype "power_in"))
      (node (ref "U10") (pin "F17") (pinfunction "DDRM_VDD12_F17") (pintype "power_in"))
      (node (ref "U10") (pin "F19") (pinfunction "DDRM_VDD12_F19") (pintype "power_in"))
      (node (ref "U10") (pin "H10") (pinfunction "VDDDDR_H10") (pintype "power_in"))
      (node (ref "U10") (pin "H15") (pinfunction "DDRM_VDD12_H15") (pintype "power_in"))
      (node (ref "U10") (pin "H17") (pinfunction "DDRM_VDD12_H17") (pintype "power_in"))
      (node (ref "U10") (pin "H19") (pinfunction "DDRM_VDD12_H19") (pintype "power_in"))
      (node (ref "U10") (pin "J13") (pinfunction "VDDDDR_J13") (pintype "power_in"))
      (node (ref "U10") (pin "J8") (pinfunction "VDDDDR_J8") (pintype "power_in"))
      (node (ref "U10") (pin "K15") (pinfunction "DDRM_VDD12_K15") (pintype "power_in"))
      (node (ref "U10") (pin "K17") (pinfunction "DDRM_VDD12_K17") (pintype "power_in"))
      (node (ref "U10") (pin "K19") (pinfunction "DDRM_VDD12_K19") (pintype "power_in"))
      (node (ref "U10") (pin "L10") (pinfunction "VDDDDR_L10") (pintype "power_in"))
      (node (ref "U10") (pin "M15") (pinfunction "DDRM_VDD12_M15") (pintype "power_in"))
      (node (ref "U10") (pin "M17") (pinfunction "DDRM_VDD12_M17") (pintype "power_in"))
      (node (ref "U10") (pin "M19") (pinfunction "DDRM_VDD12_M19") (pintype "power_in"))
      (node (ref "U10") (pin "P12") (pinfunction "VDDDDR_P12") (pintype "power_in"))
      (node (ref "U10") (pin "P15") (pinfunction "DDRM_VDD12_P15") (pintype "power_in"))
      (node (ref "U10") (pin "P17") (pinfunction "DDRM_VDD12_P17") (pintype "power_in"))
      (node (ref "U10") (pin "P19") (pinfunction "DDRM_VDD12_P19") (pintype "power_in"))
      (node (ref "U10") (pin "T17") (pinfunction "DDRM_VDD12_T17") (pintype "power_in"))
      (node (ref "U10") (pin "T19") (pinfunction "DDRM_VDD12_T19") (pintype "power_in"))
    )
    (net (code "25") (name "VDD_DDR") (class "Default")
      (node (ref "C110") (pin "1") (pinfunction "1_1") (pintype "passive"))
      (node (ref "C111") (pin "1") (pinfunction "1_1") (pintype "passive"))
      (node (ref "C21") (pin "2") (pinfunction "2_2") (pintype "passive"))
      (node (ref "C36") (pin "2") (pinfunction "2_2") (pintype "passive"))
      (node (ref "C38") (pin "2") (pinfunction "2_2") (pintype "passive"))
      (node (ref "U10") (pin "B11") (pinfunction "DDRM_VDD18_B11") (pintype "power_in"))
      (node (ref "U10") (pin "B13") (pinfunction "DDRM_VDD18_B13") (pintype "power_in"))
      (node (ref "U10") (pin "D11") (pinfunction "DDRM_VDD18_D11") (pintype "power_in"))
      (node (ref "U10") (pin "D13") (pinfunction "DDRM_VDD18_D13") (pintype "power_in"))
      (node (ref "U10") (pin "K13") (pinfunction "DDRM_VDD18_K13") (pintype "power_in"))
      (node (ref "U10") (pin "K16") (pinfunction "DDRM_VDD18_K16") (pintype "power_in"))
    )
    (net (code "26") (name "WKUP") (class "Default")
      (node (ref "U10") (pin "U2") (pinfunction "WKUP_U2") (pintype "input"))
    )
    (net (code "27") (name "nLPM") (class "Default")
      (node (ref "U10") (pin "R4") (pinfunction "PIOBU0_R4") (pintype "bidirectional"))
    )
    (net (code "28") (name "nRST") (class "Default")
      (node (ref "U10") (pin "W3") (pinfunction "NRST_W3") (pintype "input"))
    )
    (net (code "29") (name "unconnected-(U10F-CLK_AUDIO-PadW2)") (class "Default")
      (node (ref "U10") (pin "W2") (pinfunction "CLK_AUDIO_W2") (pintype "output+no_connect"))
    )
    (net (code "30") (name "unconnected-(U10F-PIOBU1-PadR5)") (class "Default")
      (node (ref "U10") (pin "R5") (pinfunction "PIOBU1_R5") (pintype "bidirectional+no_connect"))
    )
    (net (code "31") (name "unconnected-(U10F-PIOBU2-PadR3)") (class "Default")
      (node (ref "U10") (pin "R3") (pinfunction "PIOBU2_R3") (pintype "bidirectional+no_connect"))
    )
    (net (code "32") (name "unconnected-(U10F-PIOBU3-PadT4)") (class "Default")
      (node (ref "U10") (pin "T4") (pinfunction "PIOBU3_T4") (pintype "bidirectional+no_connect"))
    )
    (net (code "33") (name "unconnected-(U10F-PIOBU4-PadU3)") (class "Default")
      (node (ref "U10") (pin "U3") (pinfunction "PIOBU4_U3") (pintype "bidirectional+no_connect"))
    )
    (net (code "34") (name "unconnected-(U10F-PIOBU5-PadT5)") (class "Default")
      (node (ref "U10") (pin "T5") (pinfunction "PIOBU5_T5") (pintype "bidirectional+no_connect"))
    )
    (net (code "35") (name "unconnected-(U10F-PIOBU6-PadU5)") (class "Default")
      (node (ref "U10") (pin "U5") (pinfunction "PIOBU6_U5") (pintype "bidirectional+no_connect"))
    )
    (net (code "36") (name "unconnected-(U10F-PIOBU7-PadP5)") (class "Default")
      (node (ref "U10") (pin "P5") (pinfunction "PIOBU7_P5") (pintype "bidirectional+no_connect"))
    )
    (net (code "37") (name "unconnected-(U10F-RXD-PadR1)") (class "Default")
      (node (ref "U10") (pin "R1") (pinfunction "RXD_R1") (pintype "input+no_connect"))
    )
  )
)
